# RoverWing-cover-V1_6.net
KiCad netlist of a schematic drawn in EAGLE
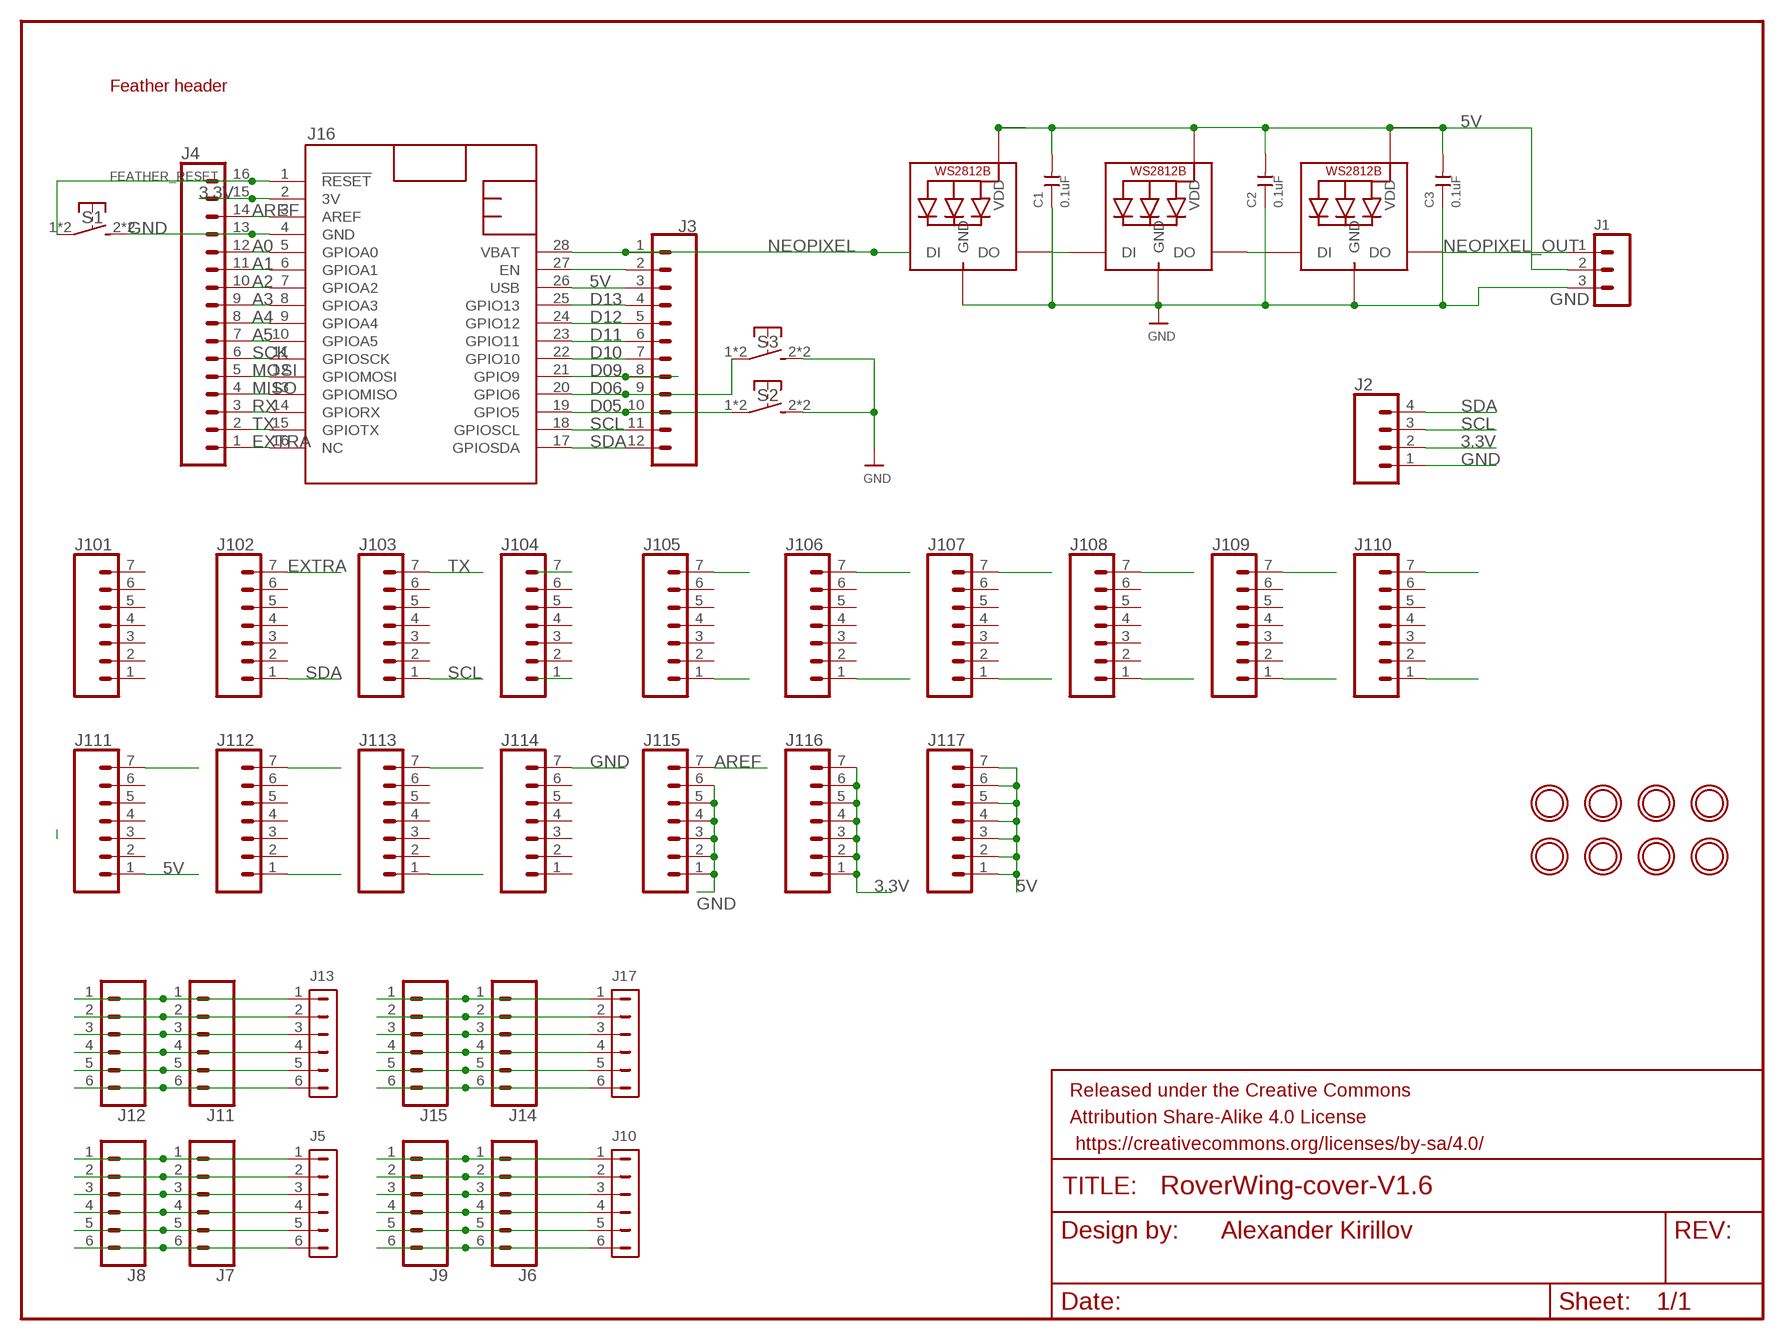
[diagram p0: schematic, sheet 1]

(export (version "E")
  (design (tool "Eeschema 10.0.6"))
  (components
    (comp (ref "C1")
      (value "0.1uF")
      (footprint "eagle-import:C0805")
      (libsource (lib "eagle-import") (part "CAP-CERAMIC-SMD-0805"))
    )
    (comp (ref "C2")
      (value "0.1uF")
      (footprint "eagle-import:C0805")
      (libsource (lib "eagle-import") (part "CAP-CERAMIC-SMD-0805"))
    )
    (comp (ref "C3")
      (value "0.1uF")
      (footprint "eagle-import:C0805")
      (libsource (lib "eagle-import") (part "CAP-CERAMIC-SMD-0805"))
    )
    (comp (ref "FRAME2")
      (value "FRAME-LETTERNO_PACKAGE")
      (footprint "eagle-import:DUMMY")
      (fields (field (name "DESIGNER") "Nobody"))
      (libsource (lib "eagle-import") (part "FRAME-LETTERNO_PACKAGE"))
    )
    (comp (ref "J1")
      (value "HEADER-PH-3PSIDEENTRY")
      (footprint "eagle-import:S3B-PH-K")
      (fields (field (name "PARTNO") "S3B-PH-K-S(LF)(SN)"))
      (libsource (lib "eagle-import") (part "HEADER-PH-3PSIDEENTRY"))
    )
    (comp (ref "J2")
      (value "CONN_04")
      (footprint "eagle-import:1X04")
      (libsource (lib "eagle-import") (part "CONN_04"))
    )
    (comp (ref "J3")
      (value "CONN_12NO_SILK")
      (footprint "eagle-import:1X12_NO_SILK")
      (libsource (lib "eagle-import") (part "CONN_12NO_SILK"))
    )
    (comp (ref "J4")
      (value "CONN_161X16_NO_SILK")
      (footprint "eagle-import:1X16_NO_SILK")
      (libsource (lib "eagle-import") (part "CONN_161X16_NO_SILK"))
    )
    (comp (ref "J5")
      (value "HEADER-PH-6PSIDEENTRY")
      (footprint "eagle-import:S6B-PH-K")
      (libsource (lib "eagle-import") (part "HEADER-PH-6PSIDEENTRY"))
    )
    (comp (ref "J6")
      (value "CONN_06NO_SILK_NO_POP")
      (footprint "eagle-import:1X06_NO_SILK")
      (libsource (lib "eagle-import") (part "CONN_06NO_SILK_NO_POP"))
    )
    (comp (ref "J7")
      (value "CONN_06NO_SILK_NO_POP")
      (footprint "eagle-import:1X06_NO_SILK")
      (libsource (lib "eagle-import") (part "CONN_06NO_SILK_NO_POP"))
    )
    (comp (ref "J8")
      (value "CONN_06NO_SILK_NO_POP")
      (footprint "eagle-import:1X06_NO_SILK")
      (libsource (lib "eagle-import") (part "CONN_06NO_SILK_NO_POP"))
    )
    (comp (ref "J9")
      (value "CONN_06NO_SILK_NO_POP")
      (footprint "eagle-import:1X06_NO_SILK")
      (libsource (lib "eagle-import") (part "CONN_06NO_SILK_NO_POP"))
    )
    (comp (ref "J10")
      (value "HEADER-PH-6PSIDEENTRY")
      (footprint "eagle-import:S6B-PH-K")
      (libsource (lib "eagle-import") (part "HEADER-PH-6PSIDEENTRY"))
    )
    (comp (ref "J11")
      (value "CONN_06NO_SILK_NO_POP")
      (footprint "eagle-import:1X06_NO_SILK")
      (libsource (lib "eagle-import") (part "CONN_06NO_SILK_NO_POP"))
    )
    (comp (ref "J12")
      (value "CONN_06NO_SILK_NO_POP")
      (footprint "eagle-import:1X06_NO_SILK")
      (libsource (lib "eagle-import") (part "CONN_06NO_SILK_NO_POP"))
    )
    (comp (ref "J13")
      (value "HEADER-PH-6PSIDEENTRY")
      (footprint "eagle-import:S6B-PH-K")
      (libsource (lib "eagle-import") (part "HEADER-PH-6PSIDEENTRY"))
    )
    (comp (ref "J14")
      (value "CONN_06NO_SILK_NO_POP")
      (footprint "eagle-import:1X06_NO_SILK")
      (libsource (lib "eagle-import") (part "CONN_06NO_SILK_NO_POP"))
    )
    (comp (ref "J15")
      (value "CONN_06NO_SILK_NO_POP")
      (footprint "eagle-import:1X06_NO_SILK")
      (libsource (lib "eagle-import") (part "CONN_06NO_SILK_NO_POP"))
    )
    (comp (ref "J16")
      (value "FEATHERWING_NODIM")
      (footprint "eagle-import:FEATHERWING_DIM")
      (libsource (lib "eagle-import") (part "FEATHERWING_NODIM"))
    )
    (comp (ref "J17")
      (value "HEADER-PH-6PSIDEENTRY")
      (footprint "eagle-import:S6B-PH-K")
      (libsource (lib "eagle-import") (part "HEADER-PH-6PSIDEENTRY"))
    )
    (comp (ref "J101")
      (value "CONN_07NO_SILK")
      (footprint "eagle-import:1X07_NO_SILK")
      (libsource (lib "eagle-import") (part "CONN_07NO_SILK"))
    )
    (comp (ref "J102")
      (value "CONN_07NO_SILK")
      (footprint "eagle-import:1X07_NO_SILK")
      (libsource (lib "eagle-import") (part "CONN_07NO_SILK"))
    )
    (comp (ref "J103")
      (value "CONN_07NO_SILK")
      (footprint "eagle-import:1X07_NO_SILK")
      (libsource (lib "eagle-import") (part "CONN_07NO_SILK"))
    )
    (comp (ref "J104")
      (value "CONN_07NO_SILK")
      (footprint "eagle-import:1X07_NO_SILK")
      (libsource (lib "eagle-import") (part "CONN_07NO_SILK"))
    )
    (comp (ref "J105")
      (value "CONN_07NO_SILK")
      (footprint "eagle-import:1X07_NO_SILK")
      (libsource (lib "eagle-import") (part "CONN_07NO_SILK"))
    )
    (comp (ref "J106")
      (value "CONN_07NO_SILK")
      (footprint "eagle-import:1X07_NO_SILK")
      (libsource (lib "eagle-import") (part "CONN_07NO_SILK"))
    )
    (comp (ref "J107")
      (value "CONN_07NO_SILK")
      (footprint "eagle-import:1X07_NO_SILK")
      (libsource (lib "eagle-import") (part "CONN_07NO_SILK"))
    )
    (comp (ref "J108")
      (value "CONN_07NO_SILK")
      (footprint "eagle-import:1X07_NO_SILK")
      (libsource (lib "eagle-import") (part "CONN_07NO_SILK"))
    )
    (comp (ref "J109")
      (value "CONN_07NO_SILK")
      (footprint "eagle-import:1X07_NO_SILK")
      (libsource (lib "eagle-import") (part "CONN_07NO_SILK"))
    )
    (comp (ref "J110")
      (value "CONN_07NO_SILK")
      (footprint "eagle-import:1X07_NO_SILK")
      (libsource (lib "eagle-import") (part "CONN_07NO_SILK"))
    )
    (comp (ref "J111")
      (value "CONN_07NO_SILK")
      (footprint "eagle-import:1X07_NO_SILK")
      (libsource (lib "eagle-import") (part "CONN_07NO_SILK"))
    )
    (comp (ref "J112")
      (value "CONN_07NO_SILK")
      (footprint "eagle-import:1X07_NO_SILK")
      (libsource (lib "eagle-import") (part "CONN_07NO_SILK"))
    )
    (comp (ref "J113")
      (value "CONN_07NO_SILK")
      (footprint "eagle-import:1X07_NO_SILK")
      (libsource (lib "eagle-import") (part "CONN_07NO_SILK"))
    )
    (comp (ref "J114")
      (value "CONN_07NO_SILK")
      (footprint "eagle-import:1X07_NO_SILK")
      (libsource (lib "eagle-import") (part "CONN_07NO_SILK"))
    )
    (comp (ref "J115")
      (value "CONN_07NO_SILK")
      (footprint "eagle-import:1X07_NO_SILK")
      (libsource (lib "eagle-import") (part "CONN_07NO_SILK"))
    )
    (comp (ref "J116")
      (value "CONN_07NO_SILK")
      (footprint "eagle-import:1X07_NO_SILK")
      (libsource (lib "eagle-import") (part "CONN_07NO_SILK"))
    )
    (comp (ref "J117")
      (value "CONN_07NO_SILK")
      (footprint "eagle-import:1X07_NO_SILK")
      (libsource (lib "eagle-import") (part "CONN_07NO_SILK"))
    )
    (comp (ref "LED1")
      (value "WS2812B3535")
      (footprint "eagle-import:LED3535")
      (fields (field (name "MANUFACTURER") "Worldsemi") (field (name "PARTNO") "WS2812B-3535 "))
      (libsource (lib "eagle-import") (part "WS2812B3535"))
    )
    (comp (ref "LED2")
      (value "WS2812B3535")
      (footprint "eagle-import:LED3535")
      (fields (field (name "MANUFACTURER") "Worldsemi") (field (name "PARTNO") "WS2812B-3535 "))
      (libsource (lib "eagle-import") (part "WS2812B3535"))
    )
    (comp (ref "LED3")
      (value "WS2812B3535")
      (footprint "eagle-import:LED3535")
      (fields (field (name "MANUFACTURER") "Worldsemi") (field (name "PARTNO") "WS2812B-3535 "))
      (libsource (lib "eagle-import") (part "WS2812B3535"))
    )
    (comp (ref "S1")
      (value "SW-TACTILE-4.5X4.5_SMD")
      (footprint "eagle-import:TL3305")
      (libsource (lib "eagle-import") (part "SW-TACTILE-4.5X4.5_SMD"))
    )
    (comp (ref "S2")
      (value "SW-TACTILE-4.5X4.5_SMD")
      (footprint "eagle-import:TL3305")
      (libsource (lib "eagle-import") (part "SW-TACTILE-4.5X4.5_SMD"))
    )
    (comp (ref "S3")
      (value "SW-TACTILE-4.5X4.5_SMD")
      (footprint "eagle-import:TL3305")
      (libsource (lib "eagle-import") (part "SW-TACTILE-4.5X4.5_SMD"))
    )
    (comp (ref "U$3")
      (value "MOUNTINGHOLE3.0_NPH")
      (footprint "eagle-import:MOUNTINGHOLE_3.0_NPH")
      (libsource (lib "eagle-import") (part "MOUNTINGHOLE3.0_NPH"))
    )
    (comp (ref "U$4")
      (value "MOUNTINGHOLE3.0_NPH")
      (footprint "eagle-import:MOUNTINGHOLE_3.0_NPH")
      (libsource (lib "eagle-import") (part "MOUNTINGHOLE3.0_NPH"))
    )
    (comp (ref "U$14")
      (value "MOUNTINGHOLE3.0_NPH")
      (footprint "eagle-import:MOUNTINGHOLE_3.0_NPH")
      (libsource (lib "eagle-import") (part "MOUNTINGHOLE3.0_NPH"))
    )
    (comp (ref "U$15")
      (value "MOUNTINGHOLE3.0_NPH")
      (footprint "eagle-import:MOUNTINGHOLE_3.0_NPH")
      (libsource (lib "eagle-import") (part "MOUNTINGHOLE3.0_NPH"))
    )
    (comp (ref "U$24")
      (value "MOUNTINGHOLE3.0_NPH")
      (footprint "eagle-import:MOUNTINGHOLE_3.0_NPH")
      (libsource (lib "eagle-import") (part "MOUNTINGHOLE3.0_NPH"))
    )
    (comp (ref "U$25")
      (value "MOUNTINGHOLE3.0_NPH")
      (footprint "eagle-import:MOUNTINGHOLE_3.0_NPH")
      (libsource (lib "eagle-import") (part "MOUNTINGHOLE3.0_NPH"))
    )
    (comp (ref "U$26")
      (value "MOUNTINGHOLE3.0_NPH")
      (footprint "eagle-import:MOUNTINGHOLE_3.0_NPH")
      (libsource (lib "eagle-import") (part "MOUNTINGHOLE3.0_NPH"))
    )
    (comp (ref "U$27")
      (value "MOUNTINGHOLE3.0_NPH")
      (footprint "eagle-import:MOUNTINGHOLE_3.0_NPH")
      (libsource (lib "eagle-import") (part "MOUNTINGHOLE3.0_NPH"))
    )
  )
  (nets
    (net (code "1") (name "/3.3V") (class "Default")
      (node (ref "J116") (pin "1") (pinfunction "1_1") (pintype "passive"))
      (node (ref "J116") (pin "2") (pinfunction "2_2") (pintype "passive"))
      (node (ref "J116") (pin "3") (pinfunction "3_3") (pintype "passive"))
      (node (ref "J116") (pin "4") (pinfunction "4_4") (pintype "passive"))
      (node (ref "J116") (pin "5") (pinfunction "5_5") (pintype "passive"))
      (node (ref "J116") (pin "6") (pinfunction "6_6") (pintype "passive"))
      (node (ref "J116") (pin "7") (pinfunction "7_7") (pintype "passive"))
      (node (ref "J16") (pin "2") (pinfunction "3V_2") (pintype "power_in"))
      (node (ref "J2") (pin "2") (pinfunction "2_2") (pintype "passive"))
      (node (ref "J4") (pin "15") (pinfunction "15_15") (pintype "passive"))
    )
    (net (code "2") (name "/5V") (class "Default")
      (node (ref "C1") (pin "2") (pinfunction "2_2") (pintype "passive"))
      (node (ref "C2") (pin "2") (pinfunction "2_2") (pintype "passive"))
      (node (ref "C3") (pin "2") (pinfunction "2_2") (pintype "passive"))
      (node (ref "J1") (pin "2") (pinfunction "2_2") (pintype "passive"))
      (node (ref "J111") (pin "1") (pinfunction "1_1") (pintype "passive"))
      (node (ref "J117") (pin "1") (pinfunction "1_1") (pintype "passive"))
      (node (ref "J117") (pin "2") (pinfunction "2_2") (pintype "passive"))
      (node (ref "J117") (pin "3") (pinfunction "3_3") (pintype "passive"))
      (node (ref "J117") (pin "4") (pinfunction "4_4") (pintype "passive"))
      (node (ref "J117") (pin "5") (pinfunction "5_5") (pintype "passive"))
      (node (ref "J117") (pin "6") (pinfunction "6_6") (pintype "passive"))
      (node (ref "J117") (pin "7") (pinfunction "7_7") (pintype "passive"))
      (node (ref "J16") (pin "26") (pinfunction "USB_26") (pintype "power_in"))
      (node (ref "J3") (pin "3") (pinfunction "3_3") (pintype "passive"))
      (node (ref "LED1") (pin "3") (pinfunction "VDD_3") (pintype "power_in"))
      (node (ref "LED2") (pin "3") (pinfunction "VDD_3") (pintype "power_in"))
      (node (ref "LED3") (pin "3") (pinfunction "VDD_3") (pintype "power_in"))
    )
    (net (code "3") (name "/A0") (class "Default")
      (node (ref "J113") (pin "7") (pinfunction "7_7") (pintype "passive"))
      (node (ref "J16") (pin "5") (pinfunction "GPIOA0_5") (pintype "bidirectional"))
      (node (ref "J4") (pin "12") (pinfunction "12_12") (pintype "passive"))
    )
    (net (code "4") (name "/A1") (class "Default")
      (node (ref "J112") (pin "7") (pinfunction "7_7") (pintype "passive"))
      (node (ref "J16") (pin "6") (pinfunction "GPIOA1_6") (pintype "bidirectional"))
      (node (ref "J4") (pin "11") (pinfunction "11_11") (pintype "passive"))
    )
    (net (code "5") (name "/A2") (class "Default")
      (node (ref "J111") (pin "7") (pinfunction "7_7") (pintype "passive"))
      (node (ref "J16") (pin "7") (pinfunction "GPIOA2_7") (pintype "bidirectional"))
      (node (ref "J4") (pin "10") (pinfunction "10_10") (pintype "passive"))
    )
    (net (code "6") (name "/A3") (class "Default")
      (node (ref "J110") (pin "7") (pinfunction "7_7") (pintype "passive"))
      (node (ref "J16") (pin "8") (pinfunction "GPIOA3_8") (pintype "bidirectional"))
      (node (ref "J4") (pin "9") (pinfunction "9_9") (pintype "passive"))
    )
    (net (code "7") (name "/A4") (class "Default")
      (node (ref "J109") (pin "7") (pinfunction "7_7") (pintype "passive"))
      (node (ref "J16") (pin "9") (pinfunction "GPIOA4_9") (pintype "bidirectional"))
      (node (ref "J4") (pin "8") (pinfunction "8_8") (pintype "passive"))
    )
    (net (code "8") (name "/A5") (class "Default")
      (node (ref "J108") (pin "7") (pinfunction "7_7") (pintype "passive"))
      (node (ref "J16") (pin "10") (pinfunction "GPIOA5_10") (pintype "bidirectional"))
      (node (ref "J4") (pin "7") (pinfunction "7_7") (pintype "passive"))
    )
    (net (code "9") (name "/AREF") (class "Default")
      (node (ref "J115") (pin "7") (pinfunction "7_7") (pintype "passive"))
      (node (ref "J16") (pin "3") (pinfunction "AREF_3") (pintype "passive"))
      (node (ref "J4") (pin "14") (pinfunction "14_14") (pintype "passive"))
    )
    (net (code "10") (name "/D05") (class "Default")
      (node (ref "J104") (pin "1") (pinfunction "1_1") (pintype "passive"))
      (node (ref "J16") (pin "19") (pinfunction "GPIO5_19") (pintype "bidirectional"))
      (node (ref "J3") (pin "10") (pinfunction "10_10") (pintype "passive"))
      (node (ref "S2") (pin "1") (pinfunction "P1_1") (pintype "passive"))
      (node (ref "S2") (pin "4") (pinfunction "P1_4") (pintype "passive"))
    )
    (net (code "11") (name "/D06") (class "Default")
      (node (ref "J105") (pin "1") (pinfunction "1_1") (pintype "passive"))
      (node (ref "J16") (pin "20") (pinfunction "GPIO6_20") (pintype "bidirectional"))
      (node (ref "J3") (pin "9") (pinfunction "9_9") (pintype "passive"))
      (node (ref "S3") (pin "1") (pinfunction "P1_1") (pintype "passive"))
      (node (ref "S3") (pin "4") (pinfunction "P1_4") (pintype "passive"))
    )
    (net (code "12") (name "/D09") (class "Default")
      (node (ref "J106") (pin "1") (pinfunction "1_1") (pintype "passive"))
      (node (ref "J16") (pin "21") (pinfunction "GPIO9_21") (pintype "bidirectional"))
      (node (ref "J3") (pin "8") (pinfunction "8_8") (pintype "passive"))
    )
    (net (code "13") (name "/D10") (class "Default")
      (node (ref "J107") (pin "1") (pinfunction "1_1") (pintype "passive"))
      (node (ref "J16") (pin "22") (pinfunction "GPIO10_22") (pintype "bidirectional"))
      (node (ref "J3") (pin "7") (pinfunction "7_7") (pintype "passive"))
    )
    (net (code "14") (name "/D11") (class "Default")
      (node (ref "J108") (pin "1") (pinfunction "1_1") (pintype "passive"))
      (node (ref "J16") (pin "23") (pinfunction "GPIO11_23") (pintype "bidirectional"))
      (node (ref "J3") (pin "6") (pinfunction "6_6") (pintype "passive"))
    )
    (net (code "15") (name "/D12") (class "Default")
      (node (ref "J109") (pin "1") (pinfunction "1_1") (pintype "passive"))
      (node (ref "J16") (pin "24") (pinfunction "GPIO12_24") (pintype "bidirectional"))
      (node (ref "J3") (pin "5") (pinfunction "5_5") (pintype "passive"))
    )
    (net (code "16") (name "/D13") (class "Default")
      (node (ref "J110") (pin "1") (pinfunction "1_1") (pintype "passive"))
      (node (ref "J16") (pin "25") (pinfunction "GPIO13_25") (pintype "bidirectional"))
      (node (ref "J3") (pin "4") (pinfunction "4_4") (pintype "passive"))
    )
    (net (code "17") (name "/EXTRA") (class "Default")
      (node (ref "J102") (pin "7") (pinfunction "7_7") (pintype "passive"))
      (node (ref "J16") (pin "16") (pinfunction "NC_16") (pintype "passive"))
      (node (ref "J4") (pin "1") (pinfunction "1_1") (pintype "passive"))
    )
    (net (code "18") (name "/FEATHER_RESET") (class "Default")
      (node (ref "J16") (pin "1") (pinfunction "~{RESET}_1") (pintype "input"))
      (node (ref "J4") (pin "16") (pinfunction "16_16") (pintype "passive"))
      (node (ref "S1") (pin "1") (pinfunction "P1_1") (pintype "passive"))
      (node (ref "S1") (pin "4") (pinfunction "P1_4") (pintype "passive"))
    )
    (net (code "19") (name "/MISO") (class "Default")
      (node (ref "J105") (pin "7") (pinfunction "7_7") (pintype "passive"))
      (node (ref "J16") (pin "13") (pinfunction "GPIOMISO_13") (pintype "bidirectional"))
      (node (ref "J4") (pin "4") (pinfunction "4_4") (pintype "passive"))
    )
    (net (code "20") (name "/MOSI") (class "Default")
      (node (ref "J106") (pin "7") (pinfunction "7_7") (pintype "passive"))
      (node (ref "J16") (pin "12") (pinfunction "GPIOMOSI_12") (pintype "bidirectional"))
      (node (ref "J4") (pin "5") (pinfunction "5_5") (pintype "passive"))
    )
    (net (code "21") (name "/N$37") (class "Default")
      (node (ref "J112") (pin "1") (pinfunction "1_1") (pintype "passive"))
      (node (ref "J16") (pin "27") (pinfunction "EN_27") (pintype "passive"))
      (node (ref "J3") (pin "2") (pinfunction "2_2") (pintype "passive"))
    )
    (net (code "22") (name "/NEOPIXEL") (class "Default")
      (node (ref "J16") (pin "28") (pinfunction "VBAT_28") (pintype "power_in"))
      (node (ref "J3") (pin "1") (pinfunction "1_1") (pintype "passive"))
      (node (ref "LED1") (pin "2") (pinfunction "DI_2") (pintype "input"))
    )
    (net (code "23") (name "/NEOPIXEL_OUT") (class "Default")
      (node (ref "J1") (pin "1") (pinfunction "1_1") (pintype "passive"))
      (node (ref "LED3") (pin "4") (pinfunction "DO_4") (pintype "output"))
    )
    (net (code "24") (name "/RX") (class "Default")
      (node (ref "J104") (pin "7") (pinfunction "7_7") (pintype "passive"))
      (node (ref "J16") (pin "14") (pinfunction "GPIORX_14") (pintype "bidirectional"))
      (node (ref "J4") (pin "3") (pinfunction "3_3") (pintype "passive"))
    )
    (net (code "25") (name "/SCK") (class "Default")
      (node (ref "J107") (pin "7") (pinfunction "7_7") (pintype "passive"))
      (node (ref "J16") (pin "11") (pinfunction "GPIOSCK_11") (pintype "bidirectional"))
      (node (ref "J4") (pin "6") (pinfunction "6_6") (pintype "passive"))
    )
    (net (code "26") (name "/SCL") (class "Default")
      (node (ref "J103") (pin "1") (pinfunction "1_1") (pintype "passive"))
      (node (ref "J16") (pin "18") (pinfunction "GPIOSCL_18") (pintype "bidirectional"))
      (node (ref "J2") (pin "3") (pinfunction "3_3") (pintype "passive"))
      (node (ref "J3") (pin "11") (pinfunction "11_11") (pintype "passive"))
    )
    (net (code "27") (name "/SDA") (class "Default")
      (node (ref "J102") (pin "1") (pinfunction "1_1") (pintype "passive"))
      (node (ref "J16") (pin "17") (pinfunction "GPIOSDA_17") (pintype "bidirectional"))
      (node (ref "J2") (pin "4") (pinfunction "4_4") (pintype "passive"))
      (node (ref "J3") (pin "12") (pinfunction "12_12") (pintype "passive"))
    )
    (net (code "28") (name "/TX") (class "Default")
      (node (ref "J103") (pin "7") (pinfunction "7_7") (pintype "passive"))
      (node (ref "J16") (pin "15") (pinfunction "GPIOTX_15") (pintype "bidirectional"))
      (node (ref "J4") (pin "2") (pinfunction "2_2") (pintype "passive"))
    )
    (net (code "29") (name "GND") (class "Default")
      (node (ref "C1") (pin "1") (pinfunction "1_1") (pintype "passive"))
      (node (ref "C2") (pin "1") (pinfunction "1_1") (pintype "passive"))
      (node (ref "C3") (pin "1") (pinfunction "1_1") (pintype "passive"))
      (node (ref "J1") (pin "3") (pinfunction "3_3") (pintype "passive"))
      (node (ref "J114") (pin "7") (pinfunction "7_7") (pintype "passive"))
      (node (ref "J115") (pin "1") (pinfunction "1_1") (pintype "passive"))
      (node (ref "J115") (pin "2") (pinfunction "2_2") (pintype "passive"))
      (node (ref "J115") (pin "3") (pinfunction "3_3") (pintype "passive"))
      (node (ref "J115") (pin "4") (pinfunction "4_4") (pintype "passive"))
      (node (ref "J115") (pin "5") (pinfunction "5_5") (pintype "passive"))
      (node (ref "J115") (pin "6") (pinfunction "6_6") (pintype "passive"))
      (node (ref "J16") (pin "4") (pinfunction "GND_4") (pintype "power_in"))
      (node (ref "J2") (pin "1") (pinfunction "1_1") (pintype "passive"))
      (node (ref "J4") (pin "13") (pinfunction "13_13") (pintype "passive"))
      (node (ref "LED1") (pin "1") (pinfunction "GND_1") (pintype "power_in"))
      (node (ref "LED2") (pin "1") (pinfunction "GND_1") (pintype "power_in"))
      (node (ref "LED3") (pin "1") (pinfunction "GND_1") (pintype "power_in"))
      (node (ref "S1") (pin "2") (pinfunction "S1_2") (pintype "passive"))
      (node (ref "S1") (pin "3") (pinfunction "S1_3") (pintype "passive"))
      (node (ref "S2") (pin "2") (pinfunction "S1_2") (pintype "passive"))
      (node (ref "S2") (pin "3") (pinfunction "S1_3") (pintype "passive"))
      (node (ref "S3") (pin "2") (pinfunction "S1_2") (pintype "passive"))
      (node (ref "S3") (pin "3") (pinfunction "S1_3") (pintype "passive"))
    )
    (net (code "30") (name "Net-(J5-Pad1)") (class "Default")
      (node (ref "J5") (pin "1") (pinfunction "1_1") (pintype "passive"))
      (node (ref "J7") (pin "1") (pinfunction "1_1") (pintype "passive"))
      (node (ref "J8") (pin "1") (pinfunction "1_1") (pintype "passive"))
    )
    (net (code "31") (name "Net-(J5-Pad2)") (class "Default")
      (node (ref "J5") (pin "2") (pinfunction "2_2") (pintype "passive"))
      (node (ref "J7") (pin "2") (pinfunction "2_2") (pintype "passive"))
      (node (ref "J8") (pin "2") (pinfunction "2_2") (pintype "passive"))
    )
    (net (code "32") (name "Net-(J5-Pad3)") (class "Default")
      (node (ref "J5") (pin "3") (pinfunction "3_3") (pintype "passive"))
      (node (ref "J7") (pin "3") (pinfunction "3_3") (pintype "passive"))
      (node (ref "J8") (pin "3") (pinfunction "3_3") (pintype "passive"))
    )
    (net (code "33") (name "Net-(J5-Pad4)") (class "Default")
      (node (ref "J5") (pin "4") (pinfunction "4_4") (pintype "passive"))
      (node (ref "J7") (pin "4") (pinfunction "4_4") (pintype "passive"))
      (node (ref "J8") (pin "4") (pinfunction "4_4") (pintype "passive"))
    )
    (net (code "34") (name "Net-(J5-Pad5)") (class "Default")
      (node (ref "J5") (pin "5") (pinfunction "5_5") (pintype "passive"))
      (node (ref "J7") (pin "5") (pinfunction "5_5") (pintype "passive"))
      (node (ref "J8") (pin "5") (pinfunction "5_5") (pintype "passive"))
    )
    (net (code "35") (name "Net-(J5-Pad6)") (class "Default")
      (node (ref "J5") (pin "6") (pinfunction "6_6") (pintype "passive"))
      (node (ref "J7") (pin "6") (pinfunction "6_6") (pintype "passive"))
      (node (ref "J8") (pin "6") (pinfunction "6_6") (pintype "passive"))
    )
    (net (code "36") (name "Net-(J10-Pad1)") (class "Default")
      (node (ref "J10") (pin "1") (pinfunction "1_1") (pintype "passive"))
      (node (ref "J6") (pin "1") (pinfunction "1_1") (pintype "passive"))
      (node (ref "J9") (pin "1") (pinfunction "1_1") (pintype "passive"))
    )
    (net (code "37") (name "Net-(J10-Pad2)") (class "Default")
      (node (ref "J10") (pin "2") (pinfunction "2_2") (pintype "passive"))
      (node (ref "J6") (pin "2") (pinfunction "2_2") (pintype "passive"))
      (node (ref "J9") (pin "2") (pinfunction "2_2") (pintype "passive"))
    )
    (net (code "38") (name "Net-(J10-Pad3)") (class "Default")
      (node (ref "J10") (pin "3") (pinfunction "3_3") (pintype "passive"))
      (node (ref "J6") (pin "3") (pinfunction "3_3") (pintype "passive"))
      (node (ref "J9") (pin "3") (pinfunction "3_3") (pintype "passive"))
    )
    (net (code "39") (name "Net-(J10-Pad4)") (class "Default")
      (node (ref "J10") (pin "4") (pinfunction "4_4") (pintype "passive"))
      (node (ref "J6") (pin "4") (pinfunction "4_4") (pintype "passive"))
      (node (ref "J9") (pin "4") (pinfunction "4_4") (pintype "passive"))
    )
    (net (code "40") (name "Net-(J10-Pad5)") (class "Default")
      (node (ref "J10") (pin "5") (pinfunction "5_5") (pintype "passive"))
      (node (ref "J6") (pin "5") (pinfunction "5_5") (pintype "passive"))
      (node (ref "J9") (pin "5") (pinfunction "5_5") (pintype "passive"))
    )
    (net (code "41") (name "Net-(J10-Pad6)") (class "Default")
      (node (ref "J10") (pin "6") (pinfunction "6_6") (pintype "passive"))
      (node (ref "J6") (pin "6") (pinfunction "6_6") (pintype "passive"))
      (node (ref "J9") (pin "6") (pinfunction "6_6") (pintype "passive"))
    )
    (net (code "42") (name "Net-(J11-Pad1)") (class "Default")
      (node (ref "J11") (pin "1") (pinfunction "1_1") (pintype "passive"))
      (node (ref "J12") (pin "1") (pinfunction "1_1") (pintype "passive"))
      (node (ref "J13") (pin "1") (pinfunction "1_1") (pintype "passive"))
    )
    (net (code "43") (name "Net-(J11-Pad2)") (class "Default")
      (node (ref "J11") (pin "2") (pinfunction "2_2") (pintype "passive"))
      (node (ref "J12") (pin "2") (pinfunction "2_2") (pintype "passive"))
      (node (ref "J13") (pin "2") (pinfunction "2_2") (pintype "passive"))
    )
    (net (code "44") (name "Net-(J11-Pad3)") (class "Default")
      (node (ref "J11") (pin "3") (pinfunction "3_3") (pintype "passive"))
      (node (ref "J12") (pin "3") (pinfunction "3_3") (pintype "passive"))
      (node (ref "J13") (pin "3") (pinfunction "3_3") (pintype "passive"))
    )
    (net (code "45") (name "Net-(J11-Pad4)") (class "Default")
      (node (ref "J11") (pin "4") (pinfunction "4_4") (pintype "passive"))
      (node (ref "J12") (pin "4") (pinfunction "4_4") (pintype "passive"))
      (node (ref "J13") (pin "4") (pinfunction "4_4") (pintype "passive"))
    )
    (net (code "46") (name "Net-(J11-Pad5)") (class "Default")
      (node (ref "J11") (pin "5") (pinfunction "5_5") (pintype "passive"))
      (node (ref "J12") (pin "5") (pinfunction "5_5") (pintype "passive"))
      (node (ref "J13") (pin "5") (pinfunction "5_5") (pintype "passive"))
    )
    (net (code "47") (name "Net-(J11-Pad6)") (class "Default")
      (node (ref "J11") (pin "6") (pinfunction "6_6") (pintype "passive"))
      (node (ref "J12") (pin "6") (pinfunction "6_6") (pintype "passive"))
      (node (ref "J13") (pin "6") (pinfunction "6_6") (pintype "passive"))
    )
    (net (code "48") (name "Net-(J14-Pad1)") (class "Default")
      (node (ref "J14") (pin "1") (pinfunction "1_1") (pintype "passive"))
      (node (ref "J15") (pin "1") (pinfunction "1_1") (pintype "passive"))
      (node (ref "J17") (pin "1") (pinfunction "1_1") (pintype "passive"))
    )
    (net (code "49") (name "Net-(J14-Pad2)") (class "Default")
      (node (ref "J14") (pin "2") (pinfunction "2_2") (pintype "passive"))
      (node (ref "J15") (pin "2") (pinfunction "2_2") (pintype "passive"))
      (node (ref "J17") (pin "2") (pinfunction "2_2") (pintype "passive"))
    )
    (net (code "50") (name "Net-(J14-Pad3)") (class "Default")
      (node (ref "J14") (pin "3") (pinfunction "3_3") (pintype "passive"))
      (node (ref "J15") (pin "3") (pinfunction "3_3") (pintype "passive"))
      (node (ref "J17") (pin "3") (pinfunction "3_3") (pintype "passive"))
    )
    (net (code "51") (name "Net-(J14-Pad4)") (class "Default")
      (node (ref "J14") (pin "4") (pinfunction "4_4") (pintype "passive"))
      (node (ref "J15") (pin "4") (pinfunction "4_4") (pintype "passive"))
      (node (ref "J17") (pin "4") (pinfunction "4_4") (pintype "passive"))
    )
    (net (code "52") (name "Net-(J14-Pad5)") (class "Default")
      (node (ref "J14") (pin "5") (pinfunction "5_5") (pintype "passive"))
      (node (ref "J15") (pin "5") (pinfunction "5_5") (pintype "passive"))
      (node (ref "J17") (pin "5") (pinfunction "5_5") (pintype "passive"))
    )
    (net (code "53") (name "Net-(J14-Pad6)") (class "Default")
      (node (ref "J14") (pin "6") (pinfunction "6_6") (pintype "passive"))
      (node (ref "J15") (pin "6") (pinfunction "6_6") (pintype "passive"))
      (node (ref "J17") (pin "6") (pinfunction "6_6") (pintype "passive"))
    )
    (net (code "54") (name "Net-(LED1-DO)") (class "Default")
      (node (ref "LED1") (pin "4") (pinfunction "DO_4") (pintype "output"))
      (node (ref "LED2") (pin "2") (pinfunction "DI_2") (pintype "input"))
    )
    (net (code "55") (name "Net-(LED2-DO)") (class "Default")
      (node (ref "LED2") (pin "4") (pinfunction "DO_4") (pintype "output"))
      (node (ref "LED3") (pin "2") (pinfunction "DI_2") (pintype "input"))
    )
    (net (code "56") (name "unconnected-(J101-Pad1)") (class "Default")
      (node (ref "J101") (pin "1") (pinfunction "1_1") (pintype "passive"))
    )
    (net (code "57") (name "unconnected-(J101-Pad2)") (class "Default")
      (node (ref "J101") (pin "2") (pinfunction "2_2") (pintype "passive"))
    )
    (net (code "58") (name "unconnected-(J101-Pad3)") (class "Default")
      (node (ref "J101") (pin "3") (pinfunction "3_3") (pintype "passive"))
    )
    (net (code "59") (name "unconnected-(J101-Pad4)") (class "Default")
      (node (ref "J101") (pin "4") (pinfunction "4_4") (pintype "passive"))
    )
    (net (code "60") (name "unconnected-(J101-Pad5)") (class "Default")
      (node (ref "J101") (pin "5") (pinfunction "5_5") (pintype "passive"))
    )
    (net (code "61") (name "unconnected-(J101-Pad6)") (class "Default")
      (node (ref "J101") (pin "6") (pinfunction "6_6") (pintype "passive"))
    )
    (net (code "62") (name "unconnected-(J101-Pad7)") (class "Default")
      (node (ref "J101") (pin "7") (pinfunction "7_7") (pintype "passive"))
    )
    (net (code "63") (name "unconnected-(J102-Pad2)") (class "Default")
      (node (ref "J102") (pin "2") (pinfunction "2_2") (pintype "passive"))
    )
    (net (code "64") (name "unconnected-(J102-Pad3)") (class "Default")
      (node (ref "J102") (pin "3") (pinfunction "3_3") (pintype "passive"))
    )
    (net (code "65") (name "unconnected-(J102-Pad4)") (class "Default")
      (node (ref "J102") (pin "4") (pinfunction "4_4") (pintype "passive"))
    )
    (net (code "66") (name "unconnected-(J102-Pad5)") (class "Default")
      (node (ref "J102") (pin "5") (pinfunction "5_5") (pintype "passive"))
    )
    (net (code "67") (name "unconnected-(J102-Pad6)") (class "Default")
      (node (ref "J102") (pin "6") (pinfunction "6_6") (pintype "passive"))
    )
    (net (code "68") (name "unconnected-(J103-Pad2)") (class "Default")
      (node (ref "J103") (pin "2") (pinfunction "2_2") (pintype "passive"))
    )
    (net (code "69") (name "unconnected-(J103-Pad3)") (class "Default")
      (node (ref "J103") (pin "3") (pinfunction "3_3") (pintype "passive"))
    )
    (net (code "70") (name "unconnected-(J103-Pad4)") (class "Default")
      (node (ref "J103") (pin "4") (pinfunction "4_4") (pintype "passive"))
    )
    (net (code "71") (name "unconnected-(J103-Pad5)") (class "Default")
      (node (ref "J103") (pin "5") (pinfunction "5_5") (pintype "passive"))
    )
    (net (code "72") (name "unconnected-(J103-Pad6)") (class "Default")
      (node (ref "J103") (pin "6") (pinfunction "6_6") (pintype "passive"))
    )
    (net (code "73") (name "unconnected-(J104-Pad2)") (class "Default")
      (node (ref "J104") (pin "2") (pinfunction "2_2") (pintype "passive"))
    )
    (net (code "74") (name "unconnected-(J104-Pad3)") (class "Default")
      (node (ref "J104") (pin "3") (pinfunction "3_3") (pintype "passive"))
    )
    (net (code "75") (name "unconnected-(J104-Pad4)") (class "Default")
      (node (ref "J104") (pin "4") (pinfunction "4_4") (pintype "passive"))
    )
    (net (code "76") (name "unconnected-(J104-Pad5)") (class "Default")
      (node (ref "J104") (pin "5") (pinfunction "5_5") (pintype "passive"))
    )
    (net (code "77") (name "unconnected-(J104-Pad6)") (class "Default")
      (node (ref "J104") (pin "6") (pinfunction "6_6") (pintype "passive"))
    )
    (net (code "78") (name "unconnected-(J105-Pad2)") (class "Default")
      (node (ref "J105") (pin "2") (pinfunction "2_2") (pintype "passive"))
    )
    (net (code "79") (name "unconnected-(J105-Pad3)") (class "Default")
      (node (ref "J105") (pin "3") (pinfunction "3_3") (pintype "passive"))
    )
    (net (code "80") (name "unconnected-(J105-Pad4)") (class "Default")
      (node (ref "J105") (pin "4") (pinfunction "4_4") (pintype "passive"))
    )
    (net (code "81") (name "unconnected-(J105-Pad5)") (class "Default")
      (node (ref "J105") (pin "5") (pinfunction "5_5") (pintype "passive"))
    )
    (net (code "82") (name "unconnected-(J105-Pad6)") (class "Default")
      (node (ref "J105") (pin "6") (pinfunction "6_6") (pintype "passive"))
    )
    (net (code "83") (name "unconnected-(J106-Pad2)") (class "Default")
      (node (ref "J106") (pin "2") (pinfunction "2_2") (pintype "passive"))
    )
    (net (code "84") (name "unconnected-(J106-Pad3)") (class "Default")
      (node (ref "J106") (pin "3") (pinfunction "3_3") (pintype "passive"))
    )
    (net (code "85") (name "unconnected-(J106-Pad4)") (class "Default")
      (node (ref "J106") (pin "4") (pinfunction "4_4") (pintype "passive"))
    )
    (net (code "86") (name "unconnected-(J106-Pad5)") (class "Default")
      (node (ref "J106") (pin "5") (pinfunction "5_5") (pintype "passive"))
    )
    (net (code "87") (name "unconnected-(J106-Pad6)") (class "Default")
      (node (ref "J106") (pin "6") (pinfunction "6_6") (pintype "passive"))
    )
    (net (code "88") (name "unconnected-(J107-Pad2)") (class "Default")
      (node (ref "J107") (pin "2") (pinfunction "2_2") (pintype "passive"))
    )
    (net (code "89") (name "unconnected-(J107-Pad3)") (class "Default")
      (node (ref "J107") (pin "3") (pinfunction "3_3") (pintype "passive"))
    )
    (net (code "90") (name "unconnected-(J107-Pad4)") (class "Default")
      (node (ref "J107") (pin "4") (pinfunction "4_4") (pintype "passive"))
    )
    (net (code "91") (name "unconnected-(J107-Pad5)") (class "Default")
      (node (ref "J107") (pin "5") (pinfunction "5_5") (pintype "passive"))
    )
    (net (code "92") (name "unconnected-(J107-Pad6)") (class "Default")
      (node (ref "J107") (pin "6") (pinfunction "6_6") (pintype "passive"))
    )
    (net (code "93") (name "unconnected-(J108-Pad2)") (class "Default")
      (node (ref "J108") (pin "2") (pinfunction "2_2") (pintype "passive"))
    )
    (net (code "94") (name "unconnected-(J108-Pad3)") (class "Default")
      (node (ref "J108") (pin "3") (pinfunction "3_3") (pintype "passive"))
    )
    (net (code "95") (name "unconnected-(J108-Pad4)") (class "Default")
      (node (ref "J108") (pin "4") (pinfunction "4_4") (pintype "passive"))
    )
    (net (code "96") (name "unconnected-(J108-Pad5)") (class "Default")
      (node (ref "J108") (pin "5") (pinfunction "5_5") (pintype "passive"))
    )
    (net (code "97") (name "unconnected-(J108-Pad6)") (class "Default")
      (node (ref "J108") (pin "6") (pinfunction "6_6") (pintype "passive"))
    )
    (net (code "98") (name "unconnected-(J109-Pad2)") (class "Default")
      (node (ref "J109") (pin "2") (pinfunction "2_2") (pintype "passive"))
    )
    (net (code "99") (name "unconnected-(J109-Pad3)") (class "Default")
      (node (ref "J109") (pin "3") (pinfunction "3_3") (pintype "passive"))
    )
    (net (code "100") (name "unconnected-(J109-Pad4)") (class "Default")
      (node (ref "J109") (pin "4") (pinfunction "4_4") (pintype "passive"))
    )
    (net (code "101") (name "unconnected-(J109-Pad5)") (class "Default")
      (node (ref "J109") (pin "5") (pinfunction "5_5") (pintype "passive"))
    )
    (net (code "102") (name "unconnected-(J109-Pad6)") (class "Default")
      (node (ref "J109") (pin "6") (pinfunction "6_6") (pintype "passive"))
    )
    (net (code "103") (name "unconnected-(J110-Pad2)") (class "Default")
      (node (ref "J110") (pin "2") (pinfunction "2_2") (pintype "passive"))
    )
    (net (code "104") (name "unconnected-(J110-Pad3)") (class "Default")
      (node (ref "J110") (pin "3") (pinfunction "3_3") (pintype "passive"))
    )
    (net (code "105") (name "unconnected-(J110-Pad4)") (class "Default")
      (node (ref "J110") (pin "4") (pinfunction "4_4") (pintype "passive"))
    )
    (net (code "106") (name "unconnected-(J110-Pad5)") (class "Default")
      (node (ref "J110") (pin "5") (pinfunction "5_5") (pintype "passive"))
    )
    (net (code "107") (name "unconnected-(J110-Pad6)") (class "Default")
      (node (ref "J110") (pin "6") (pinfunction "6_6") (pintype "passive"))
    )
    (net (code "108") (name "unconnected-(J111-Pad2)") (class "Default")
      (node (ref "J111") (pin "2") (pinfunction "2_2") (pintype "passive"))
    )
    (net (code "109") (name "unconnected-(J111-Pad3)") (class "Default")
      (node (ref "J111") (pin "3") (pinfunction "3_3") (pintype "passive"))
    )
    (net (code "110") (name "unconnected-(J111-Pad4)") (class "Default")
      (node (ref "J111") (pin "4") (pinfunction "4_4") (pintype "passive"))
    )
    (net (code "111") (name "unconnected-(J111-Pad5)") (class "Default")
      (node (ref "J111") (pin "5") (pinfunction "5_5") (pintype "passive"))
    )
    (net (code "112") (name "unconnected-(J111-Pad6)") (class "Default")
      (node (ref "J111") (pin "6") (pinfunction "6_6") (pintype "passive"))
    )
    (net (code "113") (name "unconnected-(J112-Pad2)") (class "Default")
      (node (ref "J112") (pin "2") (pinfunction "2_2") (pintype "passive"))
    )
    (net (code "114") (name "unconnected-(J112-Pad3)") (class "Default")
      (node (ref "J112") (pin "3") (pinfunction "3_3") (pintype "passive"))
    )
    (net (code "115") (name "unconnected-(J112-Pad4)") (class "Default")
      (node (ref "J112") (pin "4") (pinfunction "4_4") (pintype "passive"))
    )
    (net (code "116") (name "unconnected-(J112-Pad5)") (class "Default")
      (node (ref "J112") (pin "5") (pinfunction "5_5") (pintype "passive"))
    )
    (net (code "117") (name "unconnected-(J112-Pad6)") (class "Default")
      (node (ref "J112") (pin "6") (pinfunction "6_6") (pintype "passive"))
    )
    (net (code "118") (name "unconnected-(J113-Pad1)") (class "Default")
      (node (ref "J113") (pin "1") (pinfunction "1_1") (pintype "passive"))
    )
    (net (code "119") (name "unconnected-(J113-Pad2)") (class "Default")
      (node (ref "J113") (pin "2") (pinfunction "2_2") (pintype "passive"))
    )
    (net (code "120") (name "unconnected-(J113-Pad3)") (class "Default")
      (node (ref "J113") (pin "3") (pinfunction "3_3") (pintype "passive"))
    )
    (net (code "121") (name "unconnected-(J113-Pad4)") (class "Default")
      (node (ref "J113") (pin "4") (pinfunction "4_4") (pintype "passive"))
    )
    (net (code "122") (name "unconnected-(J113-Pad5)") (class "Default")
      (node (ref "J113") (pin "5") (pinfunction "5_5") (pintype "passive"))
    )
    (net (code "123") (name "unconnected-(J113-Pad6)") (class "Default")
      (node (ref "J113") (pin "6") (pinfunction "6_6") (pintype "passive"))
    )
    (net (code "124") (name "unconnected-(J114-Pad1)") (class "Default")
      (node (ref "J114") (pin "1") (pinfunction "1_1") (pintype "passive"))
    )
    (net (code "125") (name "unconnected-(J114-Pad2)") (class "Default")
      (node (ref "J114") (pin "2") (pinfunction "2_2") (pintype "passive"))
    )
    (net (code "126") (name "unconnected-(J114-Pad3)") (class "Default")
      (node (ref "J114") (pin "3") (pinfunction "3_3") (pintype "passive"))
    )
    (net (code "127") (name "unconnected-(J114-Pad4)") (class "Default")
      (node (ref "J114") (pin "4") (pinfunction "4_4") (pintype "passive"))
    )
    (net (code "128") (name "unconnected-(J114-Pad5)") (class "Default")
      (node (ref "J114") (pin "5") (pinfunction "5_5") (pintype "passive"))
    )
    (net (code "129") (name "unconnected-(J114-Pad6)") (class "Default")
      (node (ref "J114") (pin "6") (pinfunction "6_6") (pintype "passive"))
    )
  )
)
